# mil_battery_current_sensor.net
KiCad netlist of a schematic drawn in Altium Designer
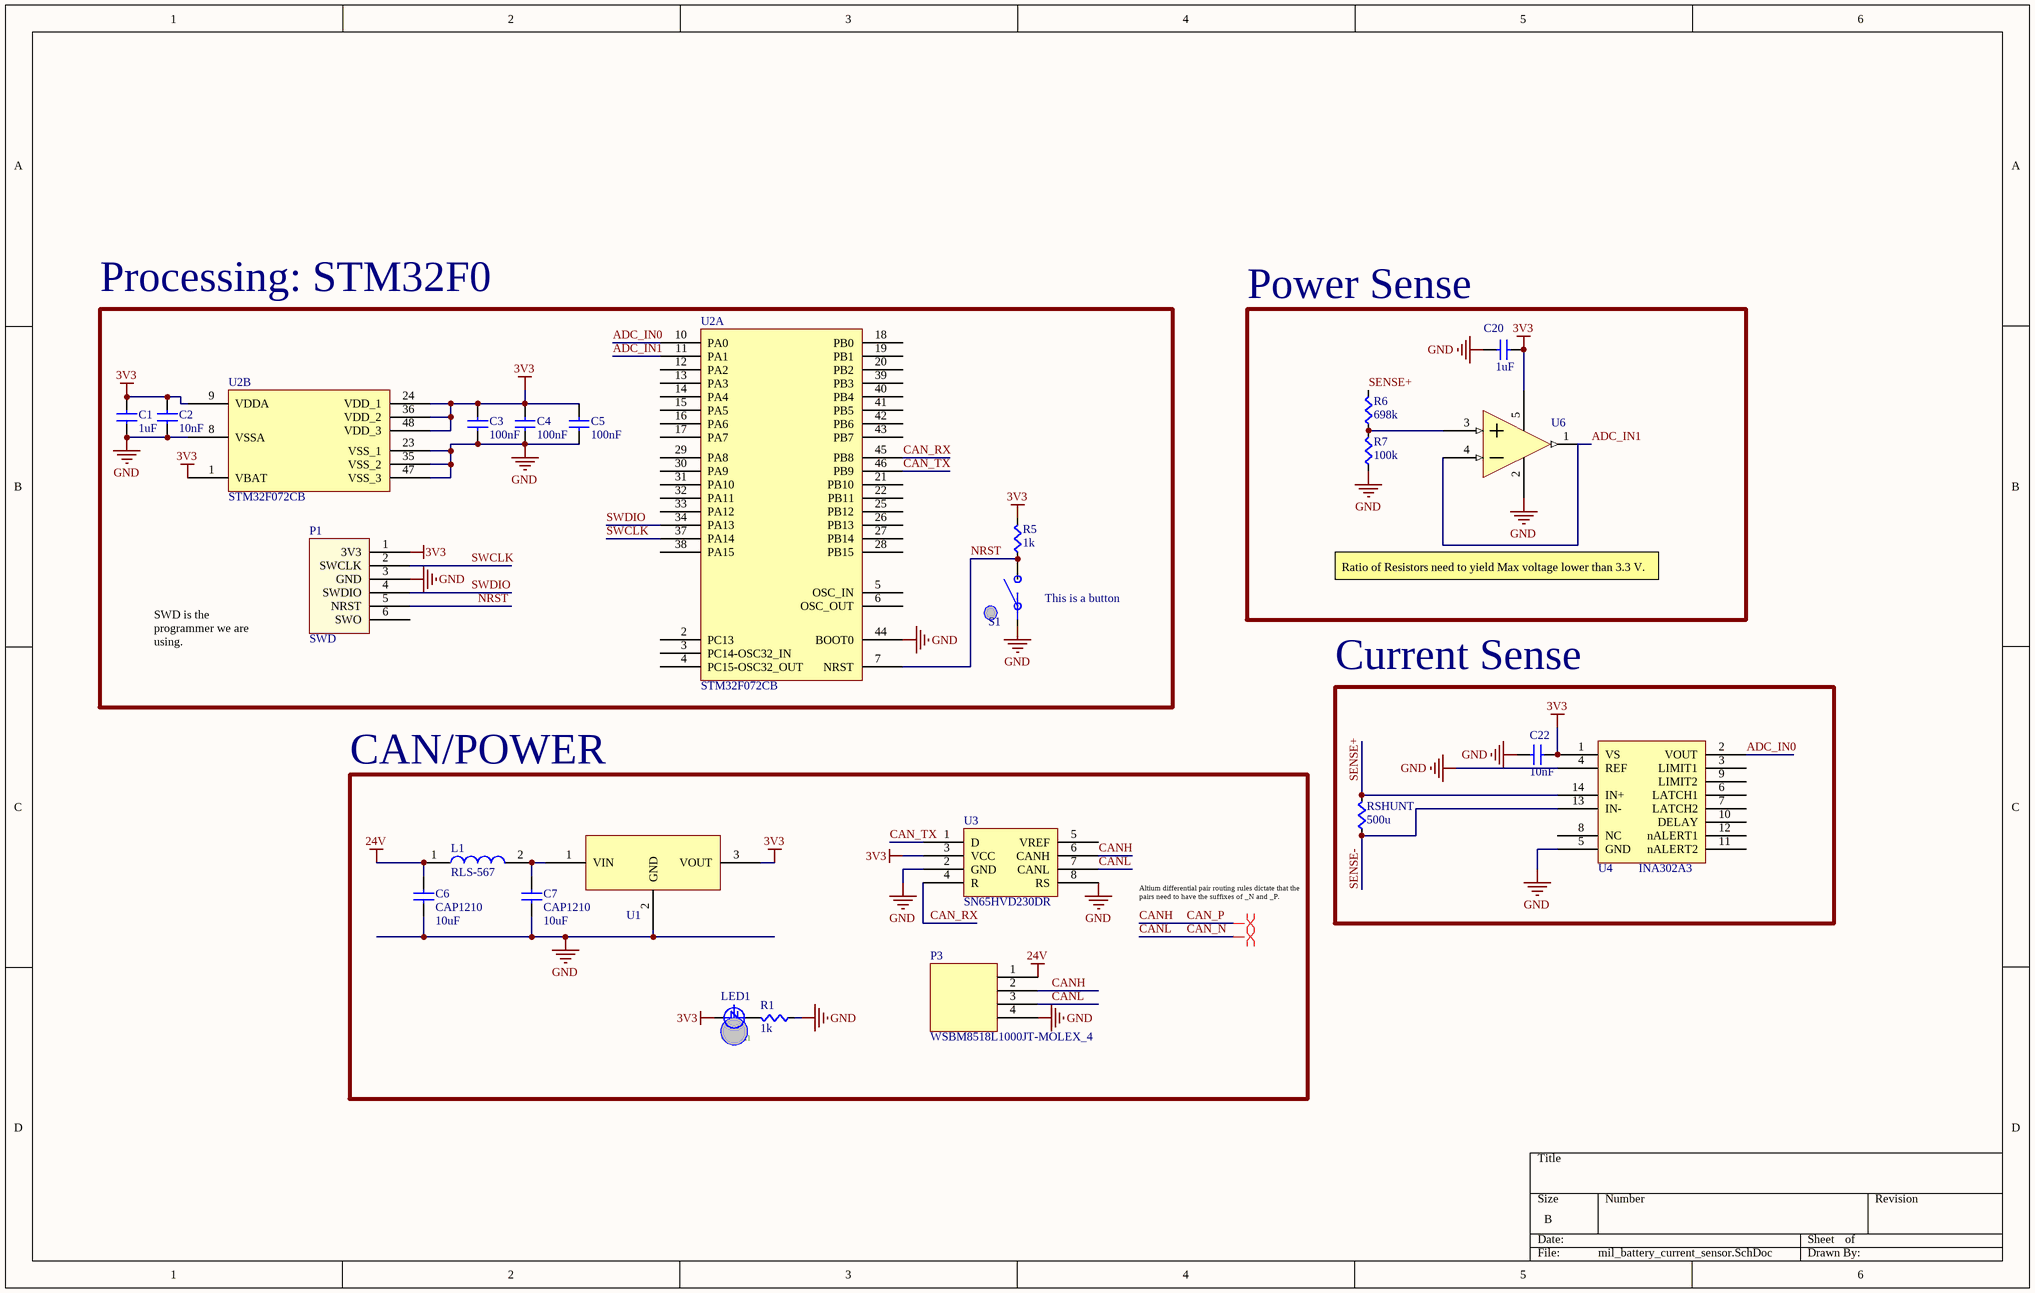
[diagram p0: mil_battery_current_sensor.SchDoc]

(export (version "E")
  (design (tool "Eeschema 10.0.6"))
  (components
    (comp (ref "C1")
      (value "1uF")
      (footprint "CAPC0603")
      (fields (field (name "MANUFACTURER PART NUMBER") "C0603C105K8PACTU") (field (name "Comment") "Cap"))
      (libsource (lib "SubjuGator8") (part "Cap"))
    )
    (comp (ref "C2")
      (value "10nF")
      (footprint "CAPC0603")
      (fields (field (name "Comment") "Cap"))
      (libsource (lib "SubjuGator8") (part "Cap"))
    )
    (comp (ref "C3")
      (value "100nF")
      (footprint "CAPC0603")
      (fields (field (name "Comment") "Cap"))
      (libsource (lib "SubjuGator8") (part "Cap"))
    )
    (comp (ref "C4")
      (value "100nF")
      (footprint "CAPC0603")
      (fields (field (name "Comment") "Cap"))
      (libsource (lib "SubjuGator8") (part "Cap"))
    )
    (comp (ref "C5")
      (value "100nF")
      (footprint "CAPC0603")
      (fields (field (name "Comment") "Cap"))
      (libsource (lib "SubjuGator8") (part "Cap"))
    )
    (comp (ref "C6")
      (value "CAP1210")
      (footprint "CAP1210")
      (description "CAP CER 10UF 50V 20% X5R 1210")
      (fields (field (name "ALTIUM_VALUE") "10uF"))
      (libsource (lib "SubjuGator8") (part "CAP1210"))
    )
    (comp (ref "C7")
      (value "CAP1210")
      (footprint "CAP1210")
      (description "CAP CER 10UF 50V 20% X5R 1210")
      (fields (field (name "ALTIUM_VALUE") "10uF"))
      (libsource (lib "SubjuGator8") (part "CAP1210"))
    )
    (comp (ref "C20")
      (value "1uF")
      (footprint "CAPC0603")
      (fields (field (name "MANUFACTURER PART NUMBER") "C0603C105K8PACTU") (field (name "Comment") "Cap"))
      (libsource (lib "SubjuGator8") (part "Cap"))
    )
    (comp (ref "C22")
      (value "10nF")
      (footprint "CAPC0603")
      (fields (field (name "Comment") "Cap"))
      (libsource (lib "SubjuGator8") (part "Cap"))
    )
    (comp (ref "L1")
      (value "RLS-567")
      (footprint "RLS567")
      (description "Inductor")
      (fields (field (name "MOUSER PART NUMBER") "919-RLS-567"))
      (libsource (lib "SubjuGator8") (part "RLS-567"))
    )
    (comp (ref "LED1")
      (value "LED")
      (footprint "LED0603")
      (fields (field (name "COLOR") "Green"))
      (libsource (lib "SubjuGator8") (part "LED"))
    )
    (comp (ref "P1")
      (value "SWD")
      (footprint "SWD_STM32")
      (description "SWD connector matching the pinout on STM Discovery Boards")
      (libsource (lib "SubjuGator8") (part "SWD_STM32"))
    )
    (comp (ref "P3")
      (value "WSBM8518L1000JT-MOLEX_4")
      (footprint "WSBM8518L1000JT-MOLEX_4")
      (description "4 pins of molex type MX150 male to female connector")
      (libsource (lib "SubjuGator8") (part "WSBM8518L1000JT-MOLEX_4"))
    )
    (comp (ref "R1")
      (value "1k")
      (footprint "RES0603")
      (fields (field (name "Comment") "Res"))
      (libsource (lib "SubjuGator8") (part "Res"))
    )
    (comp (ref "R5")
      (value "1k")
      (footprint "RES0603")
      (fields (field (name "Comment") "Res"))
      (libsource (lib "SubjuGator8") (part "Res"))
    )
    (comp (ref "R6")
      (value "698k")
      (footprint "RES0603")
      (fields (field (name "Comment") "Res"))
      (libsource (lib "SubjuGator8") (part "Res"))
    )
    (comp (ref "R7")
      (value "100k")
      (footprint "RES0603")
      (fields (field (name "Comment") "Res"))
      (libsource (lib "SubjuGator8") (part "Res"))
    )
    (comp (ref "RSHUNT")
      (value "500u")
      (footprint "WSBM8518L5000JK")
      (fields (field (name "Comment") "Res"))
      (libsource (lib "SubjuGator8") (part "Res"))
    )
    (comp (ref "S1")
      (value "Button")
      (footprint "PTS645xxxxSMTR92")
      (description "SPST Button")
      (libsource (lib "SubjuGator8") (part "Button"))
    )
    (comp (ref "U1")
      (value "R-78C3.3-1.0")
      (footprint "R-78C3.3-1.0")
      (description "CONV DC/DC 1A 3.3V OUT SIP VERT")
      (libsource (lib "SubjuGator8") (part "R-78C3.3-1.0"))
    )
    (comp (ref "U2")
      (value "STM32F072CB")
      (footprint "STM32F072CB")
      (description "MCU 32BIT 128KB FLASH 48LQFP")
      (libsource (lib "SubjuGator8") (part "STM32F072CB"))
    )
    (comp (ref "U3")
      (value "SN65HVD230DR")
      (footprint "SOIC-8pin")
      (description "IC TXRX CAN 1MBPS 3.3V 8SOIC")
      (libsource (lib "SubjuGator8") (part "SN65HVD230DR"))
    )
    (comp (ref "U4")
      (value "INA302A3")
      (footprint "INA302A2IPW")
      (description "IC CURRENT SENSING AMP 14TSSOP")
      (libsource (lib "SubjuGator8") (part "INA302A2IPW"))
    )
    (comp (ref "U6")
      (value "MCP6L01")
      (footprint "MCP6L01R")
      (description "Op Amp Rail-to-Rail 1Mhz")
      (libsource (lib "SubjuGator8") (part "MCP6L01"))
    )
  )
  (nets
    (net (code "1") (name "/ADC_IN0") (class "Default")
      (node (ref "U2") (pin "10") (pinfunction "PA0_10") (pintype "passive"))
      (node (ref "U4") (pin "2") (pinfunction "VOUT_2") (pintype "passive"))
    )
    (net (code "2") (name "/ADC_IN1") (class "Default")
      (node (ref "U2") (pin "11") (pinfunction "PA1_11") (pintype "passive"))
      (node (ref "U6") (pin "1") (pinfunction "VOUT_1") (pintype "output"))
      (node (ref "U6") (pin "4") (pinfunction "VIN-_4") (pintype "input"))
    )
    (net (code "3") (name "/CANH") (class "Default")
      (node (ref "P3") (pin "2") (pintype "passive"))
      (node (ref "U3") (pin "6") (pinfunction "CANH_6") (pintype "passive"))
    )
    (net (code "4") (name "/CANL") (class "Default")
      (node (ref "P3") (pin "3") (pintype "passive"))
      (node (ref "U3") (pin "7") (pinfunction "CANL_7") (pintype "passive"))
    )
    (net (code "5") (name "/CAN_RX") (class "Default")
      (node (ref "U2") (pin "45") (pinfunction "PB8_45") (pintype "passive"))
      (node (ref "U3") (pin "4") (pinfunction "R_4") (pintype "passive"))
    )
    (net (code "6") (name "/CAN_TX") (class "Default")
      (node (ref "U2") (pin "46") (pinfunction "PB9_46") (pintype "passive"))
      (node (ref "U3") (pin "1") (pinfunction "D_1") (pintype "passive"))
    )
    (net (code "7") (name "/NRST") (class "Default")
      (node (ref "P1") (pin "5") (pinfunction "NRST_5") (pintype "passive"))
      (node (ref "R5") (pin "2") (pinfunction "B_2") (pintype "passive"))
      (node (ref "S1") (pin "B") (pinfunction "B_B") (pintype "passive"))
      (node (ref "U2") (pin "7") (pinfunction "NRST_7") (pintype "passive"))
    )
    (net (code "8") (name "/SENSE+") (class "Default")
      (node (ref "R6") (pin "1") (pinfunction "A_1") (pintype "passive"))
      (node (ref "RSHUNT") (pin "1") (pinfunction "A_1") (pintype "passive"))
      (node (ref "U4") (pin "14") (pinfunction "IN+_14") (pintype "passive"))
    )
    (net (code "9") (name "/SENSE-") (class "Default")
      (node (ref "RSHUNT") (pin "2") (pinfunction "B_2") (pintype "passive"))
      (node (ref "U4") (pin "13") (pinfunction "IN-_13") (pintype "passive"))
    )
    (net (code "10") (name "/SWCLK") (class "Default")
      (node (ref "P1") (pin "2") (pinfunction "SWCLK_2") (pintype "passive"))
      (node (ref "U2") (pin "37") (pinfunction "PA14_37") (pintype "passive"))
    )
    (net (code "11") (name "/SWDIO") (class "Default")
      (node (ref "P1") (pin "4") (pinfunction "SWDIO_4") (pintype "passive"))
      (node (ref "U2") (pin "34") (pinfunction "PA13_34") (pintype "passive"))
    )
    (net (code "12") (name "3V3") (class "Default")
      (node (ref "C1") (pin "1") (pinfunction "A_1") (pintype "passive"))
      (node (ref "C2") (pin "1") (pinfunction "A_1") (pintype "passive"))
      (node (ref "C20") (pin "2") (pinfunction "B_2") (pintype "passive"))
      (node (ref "C22") (pin "2") (pinfunction "B_2") (pintype "passive"))
      (node (ref "C3") (pin "1") (pinfunction "A_1") (pintype "passive"))
      (node (ref "C4") (pin "1") (pinfunction "A_1") (pintype "passive"))
      (node (ref "C5") (pin "1") (pinfunction "A_1") (pintype "passive"))
      (node (ref "LED1") (pin "A") (pinfunction "A_A") (pintype "passive"))
      (node (ref "P1") (pin "1") (pinfunction "3V3_1") (pintype "passive"))
      (node (ref "R5") (pin "1") (pinfunction "A_1") (pintype "passive"))
      (node (ref "U1") (pin "3") (pinfunction "VOUT_3") (pintype "passive"))
      (node (ref "U2") (pin "1") (pinfunction "VBAT_1") (pintype "passive"))
      (node (ref "U2") (pin "24") (pinfunction "VDD_1_24") (pintype "passive"))
      (node (ref "U2") (pin "36") (pinfunction "VDD_2_36") (pintype "passive"))
      (node (ref "U2") (pin "48") (pinfunction "VDD_3_48") (pintype "passive"))
      (node (ref "U2") (pin "9") (pinfunction "VDDA_9") (pintype "passive"))
      (node (ref "U3") (pin "3") (pinfunction "VCC_3") (pintype "passive"))
      (node (ref "U4") (pin "1") (pinfunction "VS_1") (pintype "passive"))
      (node (ref "U6") (pin "5") (pinfunction "VDD_5") (pintype "power_in"))
    )
    (net (code "13") (name "24V") (class "Default")
      (node (ref "C6") (pin "1") (pinfunction "A_1") (pintype "passive"))
      (node (ref "L1") (pin "1") (pinfunction "1_1") (pintype "passive"))
      (node (ref "P3") (pin "1") (pintype "passive"))
    )
    (net (code "14") (name "GND") (class "Default")
      (node (ref "C1") (pin "2") (pinfunction "B_2") (pintype "passive"))
      (node (ref "C2") (pin "2") (pinfunction "B_2") (pintype "passive"))
      (node (ref "C20") (pin "1") (pinfunction "A_1") (pintype "passive"))
      (node (ref "C22") (pin "1") (pinfunction "A_1") (pintype "passive"))
      (node (ref "C3") (pin "2") (pinfunction "B_2") (pintype "passive"))
      (node (ref "C4") (pin "2") (pinfunction "B_2") (pintype "passive"))
      (node (ref "C5") (pin "2") (pinfunction "B_2") (pintype "passive"))
      (node (ref "C6") (pin "2") (pinfunction "B_2") (pintype "passive"))
      (node (ref "C7") (pin "2") (pinfunction "B_2") (pintype "passive"))
      (node (ref "P1") (pin "3") (pinfunction "GND_3") (pintype "passive"))
      (node (ref "P3") (pin "4") (pintype "passive"))
      (node (ref "R1") (pin "2") (pinfunction "B_2") (pintype "passive"))
      (node (ref "R7") (pin "2") (pinfunction "B_2") (pintype "passive"))
      (node (ref "S1") (pin "A") (pinfunction "A_A") (pintype "passive"))
      (node (ref "U1") (pin "2") (pinfunction "GND_2") (pintype "power_in"))
      (node (ref "U2") (pin "23") (pinfunction "VSS_1_23") (pintype "passive"))
      (node (ref "U2") (pin "35") (pinfunction "VSS_2_35") (pintype "passive"))
      (node (ref "U2") (pin "44") (pinfunction "BOOT0_44") (pintype "passive"))
      (node (ref "U2") (pin "47") (pinfunction "VSS_3_47") (pintype "passive"))
      (node (ref "U2") (pin "8") (pinfunction "VSSA_8") (pintype "passive"))
      (node (ref "U3") (pin "2") (pinfunction "GND_2") (pintype "passive"))
      (node (ref "U3") (pin "8") (pinfunction "RS_8") (pintype "passive"))
      (node (ref "U4") (pin "4") (pinfunction "REF_4") (pintype "passive"))
      (node (ref "U4") (pin "5") (pinfunction "GND_5") (pintype "passive"))
      (node (ref "U6") (pin "2") (pinfunction "VSS_2") (pintype "power_in"))
    )
    (net (code "15") (name "Net-(C7-A)") (class "Default")
      (node (ref "C7") (pin "1") (pinfunction "A_1") (pintype "passive"))
      (node (ref "L1") (pin "2") (pinfunction "2_2") (pintype "passive"))
      (node (ref "U1") (pin "1") (pinfunction "VIN_1") (pintype "passive"))
    )
    (net (code "16") (name "Net-(R1-A)") (class "Default")
      (node (ref "LED1") (pin "C") (pinfunction "C_C") (pintype "passive"))
      (node (ref "R1") (pin "1") (pinfunction "A_1") (pintype "passive"))
    )
    (net (code "17") (name "Net-(R6-B)") (class "Default")
      (node (ref "R6") (pin "2") (pinfunction "B_2") (pintype "passive"))
      (node (ref "R7") (pin "1") (pinfunction "A_1") (pintype "passive"))
      (node (ref "U6") (pin "3") (pinfunction "VIN+_3") (pintype "input"))
    )
    (net (code "18") (name "unconnected-(P1-SWO-Pad6)") (class "Default")
      (node (ref "P1") (pin "6") (pinfunction "SWO_6") (pintype "passive"))
    )
    (net (code "19") (name "unconnected-(U2A-OSC_IN-Pad5)") (class "Default")
      (node (ref "U2") (pin "5") (pinfunction "OSC_IN_5") (pintype "passive"))
    )
    (net (code "20") (name "unconnected-(U2A-OSC_OUT-Pad6)") (class "Default")
      (node (ref "U2") (pin "6") (pinfunction "OSC_OUT_6") (pintype "passive"))
    )
    (net (code "21") (name "unconnected-(U2A-PA2-Pad12)") (class "Default")
      (node (ref "U2") (pin "12") (pinfunction "PA2_12") (pintype "passive"))
    )
    (net (code "22") (name "unconnected-(U2A-PA3-Pad13)") (class "Default")
      (node (ref "U2") (pin "13") (pinfunction "PA3_13") (pintype "passive"))
    )
    (net (code "23") (name "unconnected-(U2A-PA4-Pad14)") (class "Default")
      (node (ref "U2") (pin "14") (pinfunction "PA4_14") (pintype "passive"))
    )
    (net (code "24") (name "unconnected-(U2A-PA5-Pad15)") (class "Default")
      (node (ref "U2") (pin "15") (pinfunction "PA5_15") (pintype "passive"))
    )
    (net (code "25") (name "unconnected-(U2A-PA6-Pad16)") (class "Default")
      (node (ref "U2") (pin "16") (pinfunction "PA6_16") (pintype "passive"))
    )
    (net (code "26") (name "unconnected-(U2A-PA7-Pad17)") (class "Default")
      (node (ref "U2") (pin "17") (pinfunction "PA7_17") (pintype "passive"))
    )
    (net (code "27") (name "unconnected-(U2A-PA8-Pad29)") (class "Default")
      (node (ref "U2") (pin "29") (pinfunction "PA8_29") (pintype "passive"))
    )
    (net (code "28") (name "unconnected-(U2A-PA9-Pad30)") (class "Default")
      (node (ref "U2") (pin "30") (pinfunction "PA9_30") (pintype "passive"))
    )
    (net (code "29") (name "unconnected-(U2A-PA10-Pad31)") (class "Default")
      (node (ref "U2") (pin "31") (pinfunction "PA10_31") (pintype "passive"))
    )
    (net (code "30") (name "unconnected-(U2A-PA11-Pad32)") (class "Default")
      (node (ref "U2") (pin "32") (pinfunction "PA11_32") (pintype "passive"))
    )
    (net (code "31") (name "unconnected-(U2A-PA12-Pad33)") (class "Default")
      (node (ref "U2") (pin "33") (pinfunction "PA12_33") (pintype "passive"))
    )
    (net (code "32") (name "unconnected-(U2A-PA15-Pad38)") (class "Default")
      (node (ref "U2") (pin "38") (pinfunction "PA15_38") (pintype "passive"))
    )
    (net (code "33") (name "unconnected-(U2A-PB0-Pad18)") (class "Default")
      (node (ref "U2") (pin "18") (pinfunction "PB0_18") (pintype "passive"))
    )
    (net (code "34") (name "unconnected-(U2A-PB1-Pad19)") (class "Default")
      (node (ref "U2") (pin "19") (pinfunction "PB1_19") (pintype "passive"))
    )
    (net (code "35") (name "unconnected-(U2A-PB2-Pad20)") (class "Default")
      (node (ref "U2") (pin "20") (pinfunction "PB2_20") (pintype "passive"))
    )
    (net (code "36") (name "unconnected-(U2A-PB3-Pad39)") (class "Default")
      (node (ref "U2") (pin "39") (pinfunction "PB3_39") (pintype "passive"))
    )
    (net (code "37") (name "unconnected-(U2A-PB4-Pad40)") (class "Default")
      (node (ref "U2") (pin "40") (pinfunction "PB4_40") (pintype "passive"))
    )
    (net (code "38") (name "unconnected-(U2A-PB5-Pad41)") (class "Default")
      (node (ref "U2") (pin "41") (pinfunction "PB5_41") (pintype "passive"))
    )
    (net (code "39") (name "unconnected-(U2A-PB6-Pad42)") (class "Default")
      (node (ref "U2") (pin "42") (pinfunction "PB6_42") (pintype "passive"))
    )
    (net (code "40") (name "unconnected-(U2A-PB7-Pad43)") (class "Default")
      (node (ref "U2") (pin "43") (pinfunction "PB7_43") (pintype "passive"))
    )
    (net (code "41") (name "unconnected-(U2A-PB10-Pad21)") (class "Default")
      (node (ref "U2") (pin "21") (pinfunction "PB10_21") (pintype "passive"))
    )
    (net (code "42") (name "unconnected-(U2A-PB11-Pad22)") (class "Default")
      (node (ref "U2") (pin "22") (pinfunction "PB11_22") (pintype "passive"))
    )
    (net (code "43") (name "unconnected-(U2A-PB12-Pad25)") (class "Default")
      (node (ref "U2") (pin "25") (pinfunction "PB12_25") (pintype "passive"))
    )
    (net (code "44") (name "unconnected-(U2A-PB13-Pad26)") (class "Default")
      (node (ref "U2") (pin "26") (pinfunction "PB13_26") (pintype "passive"))
    )
    (net (code "45") (name "unconnected-(U2A-PB14-Pad27)") (class "Default")
      (node (ref "U2") (pin "27") (pinfunction "PB14_27") (pintype "passive"))
    )
    (net (code "46") (name "unconnected-(U2A-PB15-Pad28)") (class "Default")
      (node (ref "U2") (pin "28") (pinfunction "PB15_28") (pintype "passive"))
    )
    (net (code "47") (name "unconnected-(U2A-PC13-Pad2)") (class "Default")
      (node (ref "U2") (pin "2") (pinfunction "PC13_2") (pintype "passive"))
    )
    (net (code "48") (name "unconnected-(U2A-PC14-OSC32_IN-Pad3)") (class "Default")
      (node (ref "U2") (pin "3") (pinfunction "PC14-OSC32_IN_3") (pintype "passive"))
    )
    (net (code "49") (name "unconnected-(U2A-PC15-OSC32_OUT-Pad4)") (class "Default")
      (node (ref "U2") (pin "4") (pinfunction "PC15-OSC32_OUT_4") (pintype "passive"))
    )
    (net (code "50") (name "unconnected-(U3-VREF-Pad5)") (class "Default")
      (node (ref "U3") (pin "5") (pinfunction "VREF_5") (pintype "passive"))
    )
    (net (code "51") (name "unconnected-(U4-DELAY-Pad10)") (class "Default")
      (node (ref "U4") (pin "10") (pinfunction "DELAY_10") (pintype "passive"))
    )
    (net (code "52") (name "unconnected-(U4-LATCH1-Pad6)") (class "Default")
      (node (ref "U4") (pin "6") (pinfunction "LATCH1_6") (pintype "passive"))
    )
    (net (code "53") (name "unconnected-(U4-LATCH2-Pad7)") (class "Default")
      (node (ref "U4") (pin "7") (pinfunction "LATCH2_7") (pintype "passive"))
    )
    (net (code "54") (name "unconnected-(U4-LIMIT1-Pad3)") (class "Default")
      (node (ref "U4") (pin "3") (pinfunction "LIMIT1_3") (pintype "passive"))
    )
    (net (code "55") (name "unconnected-(U4-LIMIT2-Pad9)") (class "Default")
      (node (ref "U4") (pin "9") (pinfunction "LIMIT2_9") (pintype "passive"))
    )
    (net (code "56") (name "unconnected-(U4-NC-Pad8)") (class "Default")
      (node (ref "U4") (pin "8") (pinfunction "NC_8") (pintype "passive"))
    )
    (net (code "57") (name "unconnected-(U4-nALERT1-Pad12)") (class "Default")
      (node (ref "U4") (pin "12") (pinfunction "nALERT1_12") (pintype "passive"))
    )
    (net (code "58") (name "unconnected-(U4-nALERT2-Pad11)") (class "Default")
      (node (ref "U4") (pin "11") (pinfunction "nALERT2_11") (pintype "passive"))
    )
  )
)
